# bldc.net
KiCad netlist of a schematic drawn in EAGLE
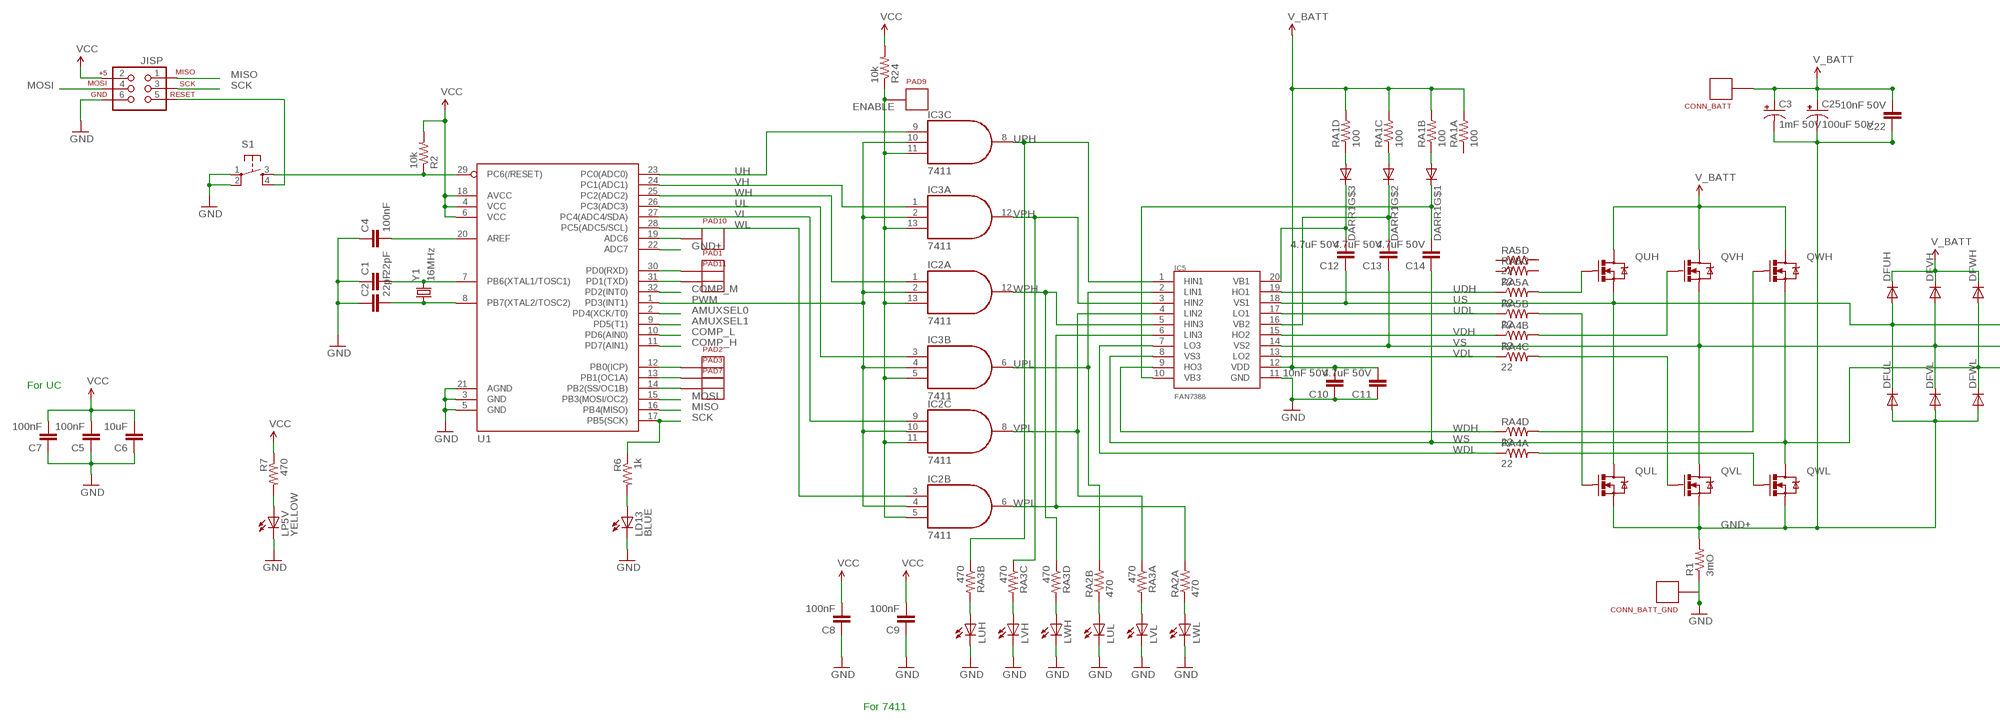
[diagram p0: schematic, sheet 1, part 1 of 2]
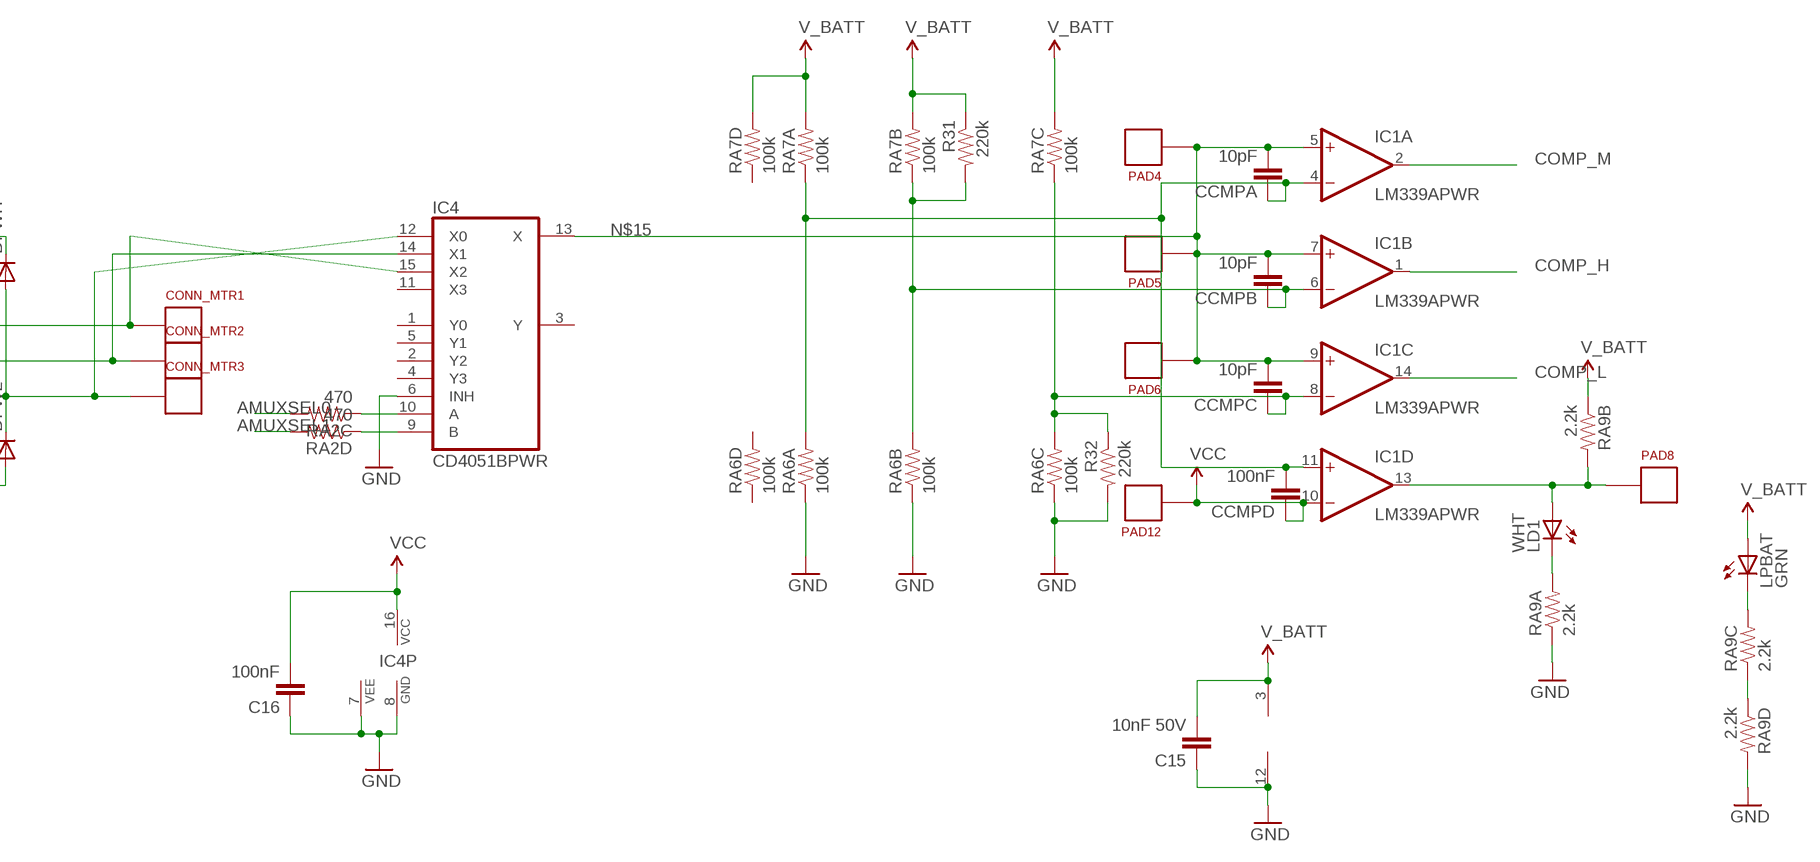
[diagram p1: schematic, sheet 1, part 2 of 2]

(export (version "E")
  (design (tool "Eeschema 10.0.6"))
  (components
    (comp (ref "C1")
      (value "22pF")
      (footprint "eagle-import:0402-CAP")
      (libsource (lib "eagle-import") (part "10NF-CER"))
    )
    (comp (ref "C2")
      (value "22pF")
      (footprint "eagle-import:0402-CAP")
      (libsource (lib "eagle-import") (part "10NF-CER"))
    )
    (comp (ref "C3")
      (value "1mF 50V")
      (footprint "eagle-import:CPOL-RADIAL-1000UF-50V")
      (libsource (lib "eagle-import") (part "CAP_POLPTH5"))
    )
    (comp (ref "C4")
      (value "100nF")
      (footprint "eagle-import:0402-CAP")
      (libsource (lib "eagle-import") (part "10NF-CER"))
    )
    (comp (ref "C5")
      (value "100nF")
      (footprint "eagle-import:0402-CAP")
      (libsource (lib "eagle-import") (part "10NF-CER"))
    )
    (comp (ref "C6")
      (value "10uF")
      (footprint "eagle-import:0805")
      (libsource (lib "eagle-import") (part "22UF-6.3V-20%(0805)"))
    )
    (comp (ref "C7")
      (value "100nF")
      (footprint "eagle-import:0402-CAP")
      (libsource (lib "eagle-import") (part "10NF-CER"))
    )
    (comp (ref "C8")
      (value "100nF")
      (footprint "eagle-import:0402-CAP")
      (libsource (lib "eagle-import") (part "10NF-CER"))
    )
    (comp (ref "C9")
      (value "100nF")
      (footprint "eagle-import:0402-CAP")
      (libsource (lib "eagle-import") (part "10NF-CER"))
    )
    (comp (ref "C10")
      (value "10nF 50V")
      (footprint "eagle-import:0402-CAP")
      (libsource (lib "eagle-import") (part "10NF-CER"))
    )
    (comp (ref "C11")
      (value "4.7uF 50V")
      (footprint "eagle-import:0805")
      (libsource (lib "eagle-import") (part "22UF-6.3V-20%(0805)"))
    )
    (comp (ref "C12")
      (value "4.7uF 50V")
      (footprint "eagle-import:0805")
      (fields (field (name "VOLTAGE") "40"))
      (libsource (lib "eagle-import") (part "22UF-6.3V-20%(0805)"))
    )
    (comp (ref "C13")
      (value "4.7uF 50V")
      (footprint "eagle-import:0805")
      (fields (field (name "VOLTAGE") "40"))
      (libsource (lib "eagle-import") (part "22UF-6.3V-20%(0805)"))
    )
    (comp (ref "C14")
      (value "4.7uF 50V")
      (footprint "eagle-import:0805")
      (fields (field (name "VOLTAGE") "40"))
      (libsource (lib "eagle-import") (part "22UF-6.3V-20%(0805)"))
    )
    (comp (ref "C15")
      (value "10nF 50V")
      (footprint "eagle-import:0402-CAP")
      (libsource (lib "eagle-import") (part "10NF-CER"))
    )
    (comp (ref "C16")
      (value "100nF")
      (footprint "eagle-import:0402-CAP")
      (libsource (lib "eagle-import") (part "10NF-CER"))
    )
    (comp (ref "C22")
      (value "10nF 50V")
      (footprint "eagle-import:0402-CAP")
      (libsource (lib "eagle-import") (part "10NF-CER"))
    )
    (comp (ref "C25")
      (value "100uF 50V")
      (footprint "eagle-import:CPOL-RADIAL-100UF-25V")
      (libsource (lib "eagle-import") (part "CAP_POLPTH1"))
    )
    (comp (ref "CCMPA")
      (value "10pF")
      (footprint "eagle-import:0402-CAP")
      (libsource (lib "eagle-import") (part "10NF-CER"))
    )
    (comp (ref "CCMPB")
      (value "10pF")
      (footprint "eagle-import:0402-CAP")
      (libsource (lib "eagle-import") (part "10NF-CER"))
    )
    (comp (ref "CCMPC")
      (value "10pF")
      (footprint "eagle-import:0402-CAP")
      (libsource (lib "eagle-import") (part "10NF-CER"))
    )
    (comp (ref "CCMPD")
      (value "100nF")
      (footprint "eagle-import:0402-CAP")
      (libsource (lib "eagle-import") (part "10NF-CER"))
    )
    (comp (ref "CONN_BATT")
      (value "CONNECTOR18AWG")
      (footprint "eagle-import:HOLE_18AWG")
      (libsource (lib "eagle-import") (part "CONNECTOR18AWG"))
    )
    (comp (ref "CONN_BATT_GND")
      (value "CONNECTOR18AWG")
      (footprint "eagle-import:HOLE_18AWG")
      (libsource (lib "eagle-import") (part "CONNECTOR18AWG"))
    )
    (comp (ref "CONN_MTR1")
      (value "CONNECTOR18AWG")
      (footprint "eagle-import:HOLE_18AWG")
      (libsource (lib "eagle-import") (part "CONNECTOR18AWG"))
    )
    (comp (ref "CONN_MTR2")
      (value "CONNECTOR18AWG")
      (footprint "eagle-import:HOLE_18AWG")
      (libsource (lib "eagle-import") (part "CONNECTOR18AWG"))
    )
    (comp (ref "CONN_MTR3")
      (value "CONNECTOR18AWG")
      (footprint "eagle-import:HOLE_18AWG")
      (libsource (lib "eagle-import") (part "CONNECTOR18AWG"))
    )
    (comp (ref "DARR1")
      (value "SD103ATW-7-F")
      (footprint "eagle-import:SOT363")
      (libsource (lib "eagle-import") (part "SD103ATW-7-F"))
    )
    (comp (ref "DFUH")
      (value "DIODESOD123W")
      (footprint "eagle-import:SOD123W(NXP)")
      (libsource (lib "eagle-import") (part "DIODESOD123W"))
    )
    (comp (ref "DFUL")
      (value "DIODESOD123W")
      (footprint "eagle-import:SOD123W(NXP)")
      (libsource (lib "eagle-import") (part "DIODESOD123W"))
    )
    (comp (ref "DFVH")
      (value "DIODESOD123W")
      (footprint "eagle-import:SOD123W(NXP)")
      (libsource (lib "eagle-import") (part "DIODESOD123W"))
    )
    (comp (ref "DFVL")
      (value "DIODESOD123W")
      (footprint "eagle-import:SOD123W(NXP)")
      (libsource (lib "eagle-import") (part "DIODESOD123W"))
    )
    (comp (ref "DFWH")
      (value "DIODESOD123W")
      (footprint "eagle-import:SOD123W(NXP)")
      (libsource (lib "eagle-import") (part "DIODESOD123W"))
    )
    (comp (ref "DFWL")
      (value "DIODESOD123W")
      (footprint "eagle-import:SOD123W(NXP)")
      (libsource (lib "eagle-import") (part "DIODESOD123W"))
    )
    (comp (ref "IC1")
      (value "LM339APWR")
      (footprint "eagle-import:TSSOP14")
      (libsource (lib "eagle-import") (part "LM339"))
    )
    (comp (ref "IC2")
      (value "7411")
      (footprint "eagle-import:TSSOP14")
      (libsource (lib "eagle-import") (part "7411"))
    )
    (comp (ref "IC3")
      (value "7411")
      (footprint "eagle-import:TSSOP14")
      (libsource (lib "eagle-import") (part "7411"))
    )
    (comp (ref "IC4")
      (value "CD4051BPWR")
      (footprint "eagle-import:TSSOP16")
      (libsource (lib "eagle-import") (part "4052"))
    )
    (comp (ref "IC5")
      (value "FAN7388")
      (footprint "eagle-import:SO20W")
      (libsource (lib "eagle-import") (part "FAN7388"))
    )
    (comp (ref "JISP")
      (value "AVR_SPI_PRG_6PTH")
      (footprint "eagle-import:2X3")
      (libsource (lib "eagle-import") (part "AVR_SPI_PRG_6PTH"))
    )
    (comp (ref "LD1")
      (value "WHT")
      (footprint "eagle-import:0603_LED")
      (libsource (lib "eagle-import") (part "LED0603"))
    )
    (comp (ref "LD13")
      (value "BLUE")
      (footprint "eagle-import:0603_LED")
      (libsource (lib "eagle-import") (part "LED0603"))
    )
    (comp (ref "LP5V")
      (value "YELLOW")
      (footprint "eagle-import:0603_LED")
      (libsource (lib "eagle-import") (part "LED0603"))
    )
    (comp (ref "LPBAT")
      (value "GRN")
      (footprint "eagle-import:0603_LED")
      (libsource (lib "eagle-import") (part "LED0603"))
    )
    (comp (ref "LUH")
      (value "LED0603")
      (footprint "eagle-import:0603_LED")
      (libsource (lib "eagle-import") (part "LED0603"))
    )
    (comp (ref "LUL")
      (value "LED0603")
      (footprint "eagle-import:0603_LED")
      (libsource (lib "eagle-import") (part "LED0603"))
    )
    (comp (ref "LVH")
      (value "LED0603")
      (footprint "eagle-import:0603_LED")
      (libsource (lib "eagle-import") (part "LED0603"))
    )
    (comp (ref "LVL")
      (value "LED0603")
      (footprint "eagle-import:0603_LED")
      (libsource (lib "eagle-import") (part "LED0603"))
    )
    (comp (ref "LWH")
      (value "LED0603")
      (footprint "eagle-import:0603_LED")
      (libsource (lib "eagle-import") (part "LED0603"))
    )
    (comp (ref "LWL")
      (value "LED0603")
      (footprint "eagle-import:0603_LED")
      (libsource (lib "eagle-import") (part "LED0603"))
    )
    (comp (ref "PAD1")
      (value "PD0")
      (footprint "eagle-import:TESTPAD")
      (libsource (lib "eagle-import") (part "CONNECTOR"))
    )
    (comp (ref "PAD2")
      (value "PB0")
      (footprint "eagle-import:TESTPAD")
      (libsource (lib "eagle-import") (part "CONNECTOR"))
    )
    (comp (ref "PAD3")
      (value "PB1")
      (footprint "eagle-import:TESTPAD")
      (libsource (lib "eagle-import") (part "CONNECTOR"))
    )
    (comp (ref "PAD4")
      (value "CMPA")
      (footprint "eagle-import:TESTPAD")
      (libsource (lib "eagle-import") (part "CONNECTOR"))
    )
    (comp (ref "PAD5")
      (value "CMPB")
      (footprint "eagle-import:TESTPAD")
      (libsource (lib "eagle-import") (part "CONNECTOR"))
    )
    (comp (ref "PAD6")
      (value "CMPC")
      (footprint "eagle-import:TESTPAD")
      (libsource (lib "eagle-import") (part "CONNECTOR"))
    )
    (comp (ref "PAD7")
      (value "PB2")
      (footprint "eagle-import:TESTPAD")
      (libsource (lib "eagle-import") (part "CONNECTOR"))
    )
    (comp (ref "PAD8")
      (value "PGD")
      (footprint "eagle-import:TESTPAD")
      (libsource (lib "eagle-import") (part "CONNECTOR"))
    )
    (comp (ref "PAD9")
      (value "ENBL")
      (footprint "eagle-import:TESTPAD")
      (libsource (lib "eagle-import") (part "CONNECTOR"))
    )
    (comp (ref "PAD10")
      (value "ADC6")
      (footprint "eagle-import:TESTPAD")
      (libsource (lib "eagle-import") (part "CONNECTOR"))
    )
    (comp (ref "PAD11")
      (value "PD1")
      (footprint "eagle-import:TESTPAD")
      (libsource (lib "eagle-import") (part "CONNECTOR"))
    )
    (comp (ref "PAD12")
      (value "VREF")
      (footprint "eagle-import:TESTPAD")
      (libsource (lib "eagle-import") (part "CONNECTOR"))
    )
    (comp (ref "QUH")
      (value "NXP_LFPAK_NFET")
      (footprint "eagle-import:POWERSO8")
      (libsource (lib "eagle-import") (part "NXP_LFPAK_NFET"))
    )
    (comp (ref "QUL")
      (value "NXP_LFPAK_NFET")
      (footprint "eagle-import:POWERSO8")
      (libsource (lib "eagle-import") (part "NXP_LFPAK_NFET"))
    )
    (comp (ref "QVH")
      (value "NXP_LFPAK_NFET")
      (footprint "eagle-import:POWERSO8")
      (libsource (lib "eagle-import") (part "NXP_LFPAK_NFET"))
    )
    (comp (ref "QVL")
      (value "NXP_LFPAK_NFET")
      (footprint "eagle-import:POWERSO8")
      (libsource (lib "eagle-import") (part "NXP_LFPAK_NFET"))
    )
    (comp (ref "QWH")
      (value "NXP_LFPAK_NFET")
      (footprint "eagle-import:POWERSO8")
      (libsource (lib "eagle-import") (part "NXP_LFPAK_NFET"))
    )
    (comp (ref "QWL")
      (value "NXP_LFPAK_NFET")
      (footprint "eagle-import:POWERSO8")
      (libsource (lib "eagle-import") (part "NXP_LFPAK_NFET"))
    )
    (comp (ref "R1")
      (value "3mO")
      (footprint "eagle-import:OAR5")
      (libsource (lib "eagle-import") (part "RESISTOROAR5"))
    )
    (comp (ref "R2")
      (value "10k")
      (footprint "eagle-import:0603-RES")
      (libsource (lib "eagle-import") (part "RESISTOR0603-RES"))
    )
    (comp (ref "R6")
      (value "1k")
      (footprint "eagle-import:0603-RES")
      (libsource (lib "eagle-import") (part "RESISTOR0603-RES"))
    )
    (comp (ref "R7")
      (value "470")
      (footprint "eagle-import:0603-RES")
      (libsource (lib "eagle-import") (part "RESISTOR0603-RES"))
    )
    (comp (ref "R24")
      (value "10k")
      (footprint "eagle-import:0603-RES")
      (libsource (lib "eagle-import") (part "RESISTOR0603-RES"))
    )
    (comp (ref "R31")
      (value "220k")
      (footprint "eagle-import:0603-RES")
      (libsource (lib "eagle-import") (part "RESISTOR0603-RES"))
    )
    (comp (ref "R32")
      (value "220k")
      (footprint "eagle-import:0603-RES")
      (libsource (lib "eagle-import") (part "RESISTOR0603-RES"))
    )
    (comp (ref "RA1")
      (value "100")
      (footprint "eagle-import:0603-ARV")
      (libsource (lib "eagle-import") (part "RESISTOR_ARRAY0603_X4"))
    )
    (comp (ref "RA2")
      (value "470")
      (footprint "eagle-import:0603-ARV")
      (libsource (lib "eagle-import") (part "RESISTOR_ARRAY0603_X4"))
    )
    (comp (ref "RA3")
      (value "470")
      (footprint "eagle-import:0603-ARV")
      (libsource (lib "eagle-import") (part "RESISTOR_ARRAY0603_X4"))
    )
    (comp (ref "RA4")
      (value "22")
      (footprint "eagle-import:0603-ARV")
      (libsource (lib "eagle-import") (part "RESISTOR_ARRAY0603_X4"))
    )
    (comp (ref "RA5")
      (value "22")
      (footprint "eagle-import:0603-ARV")
      (libsource (lib "eagle-import") (part "RESISTOR_ARRAY0603_X4"))
    )
    (comp (ref "RA6")
      (value "100k")
      (footprint "eagle-import:0603-ARV")
      (libsource (lib "eagle-import") (part "RESISTOR_ARRAY0603_X4"))
    )
    (comp (ref "RA7")
      (value "100k")
      (footprint "eagle-import:0603-ARV")
      (libsource (lib "eagle-import") (part "RESISTOR_ARRAY0603_X4"))
    )
    (comp (ref "RA9")
      (value "2.2k")
      (footprint "eagle-import:0603-ARV")
      (libsource (lib "eagle-import") (part "RESISTOR_ARRAY0603_X4"))
    )
    (comp (ref "S1")
      (value "TAC_SWITCHPTH")
      (footprint "eagle-import:TACTILE-PTH")
      (libsource (lib "eagle-import") (part "TAC_SWITCHPTH"))
    )
    (comp (ref "U1")
      (value "ATMEGA328_SMT")
      (footprint "eagle-import:TQFP32-08")
      (libsource (lib "eagle-import") (part "ATMEGA328_SMT"))
    )
    (comp (ref "Y1")
      (value "16MHz")
      (footprint "eagle-import:HC49UP")
      (libsource (lib "eagle-import") (part "CRYSTALSMD"))
    )
  )
  (nets
    (net (code "1") (name "/AMUXSEL0") (class "Default")
      (node (ref "RA2") (pin "6") (pinfunction "2_6") (pintype "passive"))
      (node (ref "U1") (pin "2") (pinfunction "PD4(XCK/T0)_2") (pintype "bidirectional"))
    )
    (net (code "2") (name "/AMUXSEL1") (class "Default")
      (node (ref "RA2") (pin "5") (pinfunction "2_5") (pintype "passive"))
      (node (ref "U1") (pin "9") (pinfunction "PD5(T1)_9") (pintype "bidirectional"))
    )
    (net (code "3") (name "/COMP_H") (class "Default")
      (node (ref "IC1") (pin "1") (pinfunction "OUT_1") (pintype "open_collector"))
      (node (ref "U1") (pin "11") (pinfunction "PD7(AIN1)_11") (pintype "bidirectional"))
    )
    (net (code "4") (name "/COMP_L") (class "Default")
      (node (ref "IC1") (pin "14") (pinfunction "OUT_14") (pintype "open_collector"))
      (node (ref "U1") (pin "10") (pinfunction "PD6(AIN0)_10") (pintype "bidirectional"))
    )
    (net (code "5") (name "/COMP_M") (class "Default")
      (node (ref "IC1") (pin "2") (pinfunction "OUT_2") (pintype "open_collector"))
      (node (ref "U1") (pin "32") (pinfunction "PD2(INT0)_32") (pintype "bidirectional"))
    )
    (net (code "6") (name "/ENABLE") (class "Default")
      (node (ref "IC2") (pin "11") (pinfunction "I2_11") (pintype "input"))
      (node (ref "IC2") (pin "13") (pinfunction "I2_13") (pintype "input"))
      (node (ref "IC2") (pin "5") (pinfunction "I2_5") (pintype "input"))
      (node (ref "IC3") (pin "11") (pinfunction "I2_11") (pintype "input"))
      (node (ref "IC3") (pin "13") (pinfunction "I2_13") (pintype "input"))
      (node (ref "IC3") (pin "5") (pinfunction "I2_5") (pintype "input"))
      (node (ref "PAD9") (pin "P") (pinfunction "P_P") (pintype "bidirectional"))
      (node (ref "R24") (pin "1") (pinfunction "1_1") (pintype "passive"))
    )
    (net (code "7") (name "/GND+") (class "Default")
      (node (ref "C22") (pin "1") (pinfunction "1_1") (pintype "passive"))
      (node (ref "C25") (pin "2") (pinfunction "-_2") (pintype "passive"))
      (node (ref "C3") (pin "2") (pinfunction "-_2") (pintype "passive"))
      (node (ref "DFUL") (pin "A") (pinfunction "A_A") (pintype "passive"))
      (node (ref "DFVL") (pin "A") (pinfunction "A_A") (pintype "passive"))
      (node (ref "DFWL") (pin "A") (pinfunction "A_A") (pintype "passive"))
      (node (ref "QUL") (pin "P1") (pinfunction "S_P1") (pintype "passive"))
      (node (ref "QUL") (pin "P2") (pinfunction "S_P2") (pintype "passive"))
      (node (ref "QUL") (pin "P3") (pinfunction "S_P3") (pintype "passive"))
      (node (ref "QVL") (pin "P1") (pinfunction "S_P1") (pintype "passive"))
      (node (ref "QVL") (pin "P2") (pinfunction "S_P2") (pintype "passive"))
      (node (ref "QVL") (pin "P3") (pinfunction "S_P3") (pintype "passive"))
      (node (ref "QWL") (pin "P1") (pinfunction "S_P1") (pintype "passive"))
      (node (ref "QWL") (pin "P2") (pinfunction "S_P2") (pintype "passive"))
      (node (ref "QWL") (pin "P3") (pinfunction "S_P3") (pintype "passive"))
      (node (ref "R1") (pin "P$2") (pinfunction "2_P$2") (pintype "passive"))
      (node (ref "U1") (pin "22") (pinfunction "ADC7_22") (pintype "bidirectional"))
    )
    (net (code "8") (name "/MISO") (class "Default")
      (node (ref "JISP") (pin "1") (pinfunction "1_1") (pintype "passive"))
      (node (ref "U1") (pin "16") (pinfunction "PB4(MISO)_16") (pintype "bidirectional"))
    )
    (net (code "9") (name "/MOSI") (class "Default")
      (node (ref "JISP") (pin "4") (pinfunction "4_4") (pintype "passive"))
      (node (ref "U1") (pin "15") (pinfunction "PB3(MOSI/OC2)_15") (pintype "bidirectional"))
    )
    (net (code "10") (name "/N$15") (class "Default")
      (node (ref "CCMPA") (pin "2") (pinfunction "2_2") (pintype "passive"))
      (node (ref "CCMPB") (pin "2") (pinfunction "2_2") (pintype "passive"))
      (node (ref "CCMPC") (pin "2") (pinfunction "2_2") (pintype "passive"))
      (node (ref "IC1") (pin "5") (pinfunction "+IN_5") (pintype "input"))
      (node (ref "IC1") (pin "7") (pinfunction "+IN_7") (pintype "input"))
      (node (ref "IC1") (pin "9") (pinfunction "+IN_9") (pintype "input"))
      (node (ref "IC4") (pin "13") (pinfunction "X_13") (pintype "bidirectional"))
      (node (ref "PAD4") (pin "P") (pinfunction "P_P") (pintype "bidirectional"))
      (node (ref "PAD5") (pin "P") (pinfunction "P_P") (pintype "bidirectional"))
      (node (ref "PAD6") (pin "P") (pinfunction "P_P") (pintype "bidirectional"))
    )
    (net (code "11") (name "/PWM") (class "Default")
      (node (ref "IC2") (pin "10") (pinfunction "I1_10") (pintype "input"))
      (node (ref "IC2") (pin "2") (pinfunction "I1_2") (pintype "input"))
      (node (ref "IC2") (pin "4") (pinfunction "I1_4") (pintype "input"))
      (node (ref "IC3") (pin "10") (pinfunction "I1_10") (pintype "input"))
      (node (ref "IC3") (pin "2") (pinfunction "I1_2") (pintype "input"))
      (node (ref "IC3") (pin "4") (pinfunction "I1_4") (pintype "input"))
      (node (ref "U1") (pin "1") (pinfunction "PD3(INT1)_1") (pintype "bidirectional"))
    )
    (net (code "12") (name "/SCK") (class "Default")
      (node (ref "JISP") (pin "3") (pinfunction "3_3") (pintype "passive"))
      (node (ref "R6") (pin "1") (pinfunction "1_1") (pintype "passive"))
      (node (ref "U1") (pin "17") (pinfunction "PB5(SCK)_17") (pintype "bidirectional"))
    )
    (net (code "13") (name "/UDH") (class "Default")
      (node (ref "IC5") (pin "19") (pinfunction "HO1_19") (pintype "bidirectional"))
      (node (ref "RA5") (pin "1") (pinfunction "1_1") (pintype "passive"))
    )
    (net (code "14") (name "/UDL") (class "Default")
      (node (ref "IC5") (pin "17") (pinfunction "LO1_17") (pintype "bidirectional"))
      (node (ref "RA5") (pin "2") (pinfunction "1_2") (pintype "passive"))
    )
    (net (code "15") (name "/UH") (class "Default")
      (node (ref "IC3") (pin "9") (pinfunction "I0_9") (pintype "input"))
      (node (ref "U1") (pin "23") (pinfunction "PC0(ADC0)_23") (pintype "bidirectional"))
    )
    (net (code "16") (name "/UL") (class "Default")
      (node (ref "IC3") (pin "3") (pinfunction "I0_3") (pintype "input"))
      (node (ref "U1") (pin "26") (pinfunction "PC3(ADC3)_26") (pintype "bidirectional"))
    )
    (net (code "17") (name "/UPH") (class "Default")
      (node (ref "IC3") (pin "8") (pinfunction "O_8") (pintype "output"))
      (node (ref "IC5") (pin "1") (pinfunction "HIN1_1") (pintype "bidirectional"))
      (node (ref "RA3") (pin "2") (pinfunction "1_2") (pintype "passive"))
    )
    (net (code "18") (name "/UPL") (class "Default")
      (node (ref "IC3") (pin "6") (pinfunction "O_6") (pintype "output"))
      (node (ref "IC5") (pin "2") (pinfunction "LIN1_2") (pintype "bidirectional"))
      (node (ref "RA2") (pin "7") (pinfunction "2_7") (pintype "passive"))
    )
    (net (code "19") (name "/US") (class "Default")
      (node (ref "C12") (pin "1") (pinfunction "1_1") (pintype "passive"))
      (node (ref "CONN_MTR1") (pin "P$1") (pinfunction "P_P$1") (pintype "bidirectional"))
      (node (ref "DFUH") (pin "A") (pinfunction "A_A") (pintype "passive"))
      (node (ref "DFUL") (pin "C") (pinfunction "C_C") (pintype "passive"))
      (node (ref "IC4") (pin "15") (pinfunction "X2_15") (pintype "bidirectional"))
      (node (ref "IC5") (pin "18") (pinfunction "VS1_18") (pintype "bidirectional"))
      (node (ref "QUH") (pin "P1") (pinfunction "S_P1") (pintype "passive"))
      (node (ref "QUH") (pin "P2") (pinfunction "S_P2") (pintype "passive"))
      (node (ref "QUH") (pin "P3") (pinfunction "S_P3") (pintype "passive"))
      (node (ref "QUL") (pin "P$1") (pinfunction "D_P$1") (pintype "passive"))
      (node (ref "QUL") (pin "P$10") (pinfunction "D_P$10") (pintype "passive"))
      (node (ref "QUL") (pin "P$11") (pinfunction "D_P$11") (pintype "passive"))
      (node (ref "QUL") (pin "P$12") (pinfunction "D_P$12") (pintype "passive"))
      (node (ref "QUL") (pin "P$13") (pinfunction "D_P$13") (pintype "passive"))
      (node (ref "QUL") (pin "P$14") (pinfunction "D_P$14") (pintype "passive"))
      (node (ref "QUL") (pin "P$15") (pinfunction "D_P$15") (pintype "passive"))
      (node (ref "QUL") (pin "P$16") (pinfunction "D_P$16") (pintype "passive"))
      (node (ref "QUL") (pin "P$17") (pinfunction "D_P$17") (pintype "passive"))
      (node (ref "QUL") (pin "P$19") (pinfunction "D_P$19") (pintype "passive"))
      (node (ref "QUL") (pin "P$20") (pinfunction "D_P$20") (pintype "passive"))
      (node (ref "QUL") (pin "P$21") (pinfunction "D_P$21") (pintype "passive"))
      (node (ref "QUL") (pin "P$5") (pinfunction "D_P$5") (pintype "passive"))
      (node (ref "QUL") (pin "P$6") (pinfunction "D_P$6") (pintype "passive"))
      (node (ref "QUL") (pin "P$7") (pinfunction "D_P$7") (pintype "passive"))
      (node (ref "QUL") (pin "P$8") (pinfunction "D_P$8") (pintype "passive"))
      (node (ref "QUL") (pin "P$9") (pinfunction "D_P$9") (pintype "passive"))
    )
    (net (code "20") (name "/VDH") (class "Default")
      (node (ref "IC5") (pin "15") (pinfunction "HO2_15") (pintype "bidirectional"))
      (node (ref "RA4") (pin "2") (pinfunction "1_2") (pintype "passive"))
    )
    (net (code "21") (name "/VDL") (class "Default")
      (node (ref "IC5") (pin "13") (pinfunction "LO2_13") (pintype "bidirectional"))
      (node (ref "RA4") (pin "3") (pinfunction "1_3") (pintype "passive"))
    )
    (net (code "22") (name "/VH") (class "Default")
      (node (ref "IC3") (pin "1") (pinfunction "I0_1") (pintype "input"))
      (node (ref "U1") (pin "24") (pinfunction "PC1(ADC1)_24") (pintype "bidirectional"))
    )
    (net (code "23") (name "/VL") (class "Default")
      (node (ref "IC2") (pin "9") (pinfunction "I0_9") (pintype "input"))
      (node (ref "U1") (pin "27") (pinfunction "PC4(ADC4/SDA)_27") (pintype "bidirectional"))
    )
    (net (code "24") (name "/VPH") (class "Default")
      (node (ref "IC3") (pin "12") (pinfunction "O_12") (pintype "output"))
      (node (ref "IC5") (pin "3") (pinfunction "HIN2_3") (pintype "bidirectional"))
      (node (ref "RA3") (pin "3") (pinfunction "1_3") (pintype "passive"))
    )
    (net (code "25") (name "/VPL") (class "Default")
      (node (ref "IC2") (pin "8") (pinfunction "O_8") (pintype "output"))
      (node (ref "IC5") (pin "4") (pinfunction "LIN2_4") (pintype "bidirectional"))
      (node (ref "RA3") (pin "1") (pinfunction "1_1") (pintype "passive"))
    )
    (net (code "26") (name "/VS") (class "Default")
      (node (ref "C13") (pin "1") (pinfunction "1_1") (pintype "passive"))
      (node (ref "CONN_MTR2") (pin "P$1") (pinfunction "P_P$1") (pintype "bidirectional"))
      (node (ref "DFVH") (pin "A") (pinfunction "A_A") (pintype "passive"))
      (node (ref "DFVL") (pin "C") (pinfunction "C_C") (pintype "passive"))
      (node (ref "IC4") (pin "14") (pinfunction "X1_14") (pintype "bidirectional"))
      (node (ref "IC5") (pin "14") (pinfunction "VS2_14") (pintype "bidirectional"))
      (node (ref "QVH") (pin "P1") (pinfunction "S_P1") (pintype "passive"))
      (node (ref "QVH") (pin "P2") (pinfunction "S_P2") (pintype "passive"))
      (node (ref "QVH") (pin "P3") (pinfunction "S_P3") (pintype "passive"))
      (node (ref "QVL") (pin "P$1") (pinfunction "D_P$1") (pintype "passive"))
      (node (ref "QVL") (pin "P$10") (pinfunction "D_P$10") (pintype "passive"))
      (node (ref "QVL") (pin "P$11") (pinfunction "D_P$11") (pintype "passive"))
      (node (ref "QVL") (pin "P$12") (pinfunction "D_P$12") (pintype "passive"))
      (node (ref "QVL") (pin "P$13") (pinfunction "D_P$13") (pintype "passive"))
      (node (ref "QVL") (pin "P$14") (pinfunction "D_P$14") (pintype "passive"))
      (node (ref "QVL") (pin "P$15") (pinfunction "D_P$15") (pintype "passive"))
      (node (ref "QVL") (pin "P$16") (pinfunction "D_P$16") (pintype "passive"))
      (node (ref "QVL") (pin "P$17") (pinfunction "D_P$17") (pintype "passive"))
      (node (ref "QVL") (pin "P$19") (pinfunction "D_P$19") (pintype "passive"))
      (node (ref "QVL") (pin "P$20") (pinfunction "D_P$20") (pintype "passive"))
      (node (ref "QVL") (pin "P$21") (pinfunction "D_P$21") (pintype "passive"))
      (node (ref "QVL") (pin "P$5") (pinfunction "D_P$5") (pintype "passive"))
      (node (ref "QVL") (pin "P$6") (pinfunction "D_P$6") (pintype "passive"))
      (node (ref "QVL") (pin "P$7") (pinfunction "D_P$7") (pintype "passive"))
      (node (ref "QVL") (pin "P$8") (pinfunction "D_P$8") (pintype "passive"))
      (node (ref "QVL") (pin "P$9") (pinfunction "D_P$9") (pintype "passive"))
    )
    (net (code "27") (name "/WDH") (class "Default")
      (node (ref "IC5") (pin "9") (pinfunction "HO3_9") (pintype "bidirectional"))
      (node (ref "RA4") (pin "4") (pinfunction "1_4") (pintype "passive"))
    )
    (net (code "28") (name "/WDL") (class "Default")
      (node (ref "IC5") (pin "7") (pinfunction "LO3_7") (pintype "bidirectional"))
      (node (ref "RA4") (pin "1") (pinfunction "1_1") (pintype "passive"))
    )
    (net (code "29") (name "/WH") (class "Default")
      (node (ref "IC2") (pin "1") (pinfunction "I0_1") (pintype "input"))
      (node (ref "U1") (pin "25") (pinfunction "PC2(ADC2)_25") (pintype "bidirectional"))
    )
    (net (code "30") (name "/WL") (class "Default")
      (node (ref "IC2") (pin "3") (pinfunction "I0_3") (pintype "input"))
      (node (ref "U1") (pin "28") (pinfunction "PC5(ADC5/SCL)_28") (pintype "bidirectional"))
    )
    (net (code "31") (name "/WPH") (class "Default")
      (node (ref "IC2") (pin "12") (pinfunction "O_12") (pintype "output"))
      (node (ref "IC5") (pin "5") (pinfunction "HIN3_5") (pintype "bidirectional"))
      (node (ref "RA3") (pin "4") (pinfunction "1_4") (pintype "passive"))
    )
    (net (code "32") (name "/WPL") (class "Default")
      (node (ref "IC2") (pin "6") (pinfunction "O_6") (pintype "output"))
      (node (ref "IC5") (pin "6") (pinfunction "LIN3_6") (pintype "bidirectional"))
      (node (ref "RA2") (pin "8") (pinfunction "2_8") (pintype "passive"))
    )
    (net (code "33") (name "/WS") (class "Default")
      (node (ref "C14") (pin "1") (pinfunction "1_1") (pintype "passive"))
      (node (ref "CONN_MTR3") (pin "P$1") (pinfunction "P_P$1") (pintype "bidirectional"))
      (node (ref "DFWH") (pin "A") (pinfunction "A_A") (pintype "passive"))
      (node (ref "DFWL") (pin "C") (pinfunction "C_C") (pintype "passive"))
      (node (ref "IC4") (pin "12") (pinfunction "X0_12") (pintype "bidirectional"))
      (node (ref "IC5") (pin "8") (pinfunction "VS3_8") (pintype "bidirectional"))
      (node (ref "QWH") (pin "P1") (pinfunction "S_P1") (pintype "passive"))
      (node (ref "QWH") (pin "P2") (pinfunction "S_P2") (pintype "passive"))
      (node (ref "QWH") (pin "P3") (pinfunction "S_P3") (pintype "passive"))
      (node (ref "QWL") (pin "P$1") (pinfunction "D_P$1") (pintype "passive"))
      (node (ref "QWL") (pin "P$10") (pinfunction "D_P$10") (pintype "passive"))
      (node (ref "QWL") (pin "P$11") (pinfunction "D_P$11") (pintype "passive"))
      (node (ref "QWL") (pin "P$12") (pinfunction "D_P$12") (pintype "passive"))
      (node (ref "QWL") (pin "P$13") (pinfunction "D_P$13") (pintype "passive"))
      (node (ref "QWL") (pin "P$14") (pinfunction "D_P$14") (pintype "passive"))
      (node (ref "QWL") (pin "P$15") (pinfunction "D_P$15") (pintype "passive"))
      (node (ref "QWL") (pin "P$16") (pinfunction "D_P$16") (pintype "passive"))
      (node (ref "QWL") (pin "P$17") (pinfunction "D_P$17") (pintype "passive"))
      (node (ref "QWL") (pin "P$19") (pinfunction "D_P$19") (pintype "passive"))
      (node (ref "QWL") (pin "P$20") (pinfunction "D_P$20") (pintype "passive"))
      (node (ref "QWL") (pin "P$21") (pinfunction "D_P$21") (pintype "passive"))
      (node (ref "QWL") (pin "P$5") (pinfunction "D_P$5") (pintype "passive"))
      (node (ref "QWL") (pin "P$6") (pinfunction "D_P$6") (pintype "passive"))
      (node (ref "QWL") (pin "P$7") (pinfunction "D_P$7") (pintype "passive"))
      (node (ref "QWL") (pin "P$8") (pinfunction "D_P$8") (pintype "passive"))
      (node (ref "QWL") (pin "P$9") (pinfunction "D_P$9") (pintype "passive"))
    )
    (net (code "34") (name "GND") (class "Default")
      (node (ref "C1") (pin "1") (pinfunction "1_1") (pintype "passive"))
      (node (ref "C10") (pin "1") (pinfunction "1_1") (pintype "passive"))
      (node (ref "C11") (pin "1") (pinfunction "1_1") (pintype "passive"))
      (node (ref "C15") (pin "1") (pinfunction "1_1") (pintype "passive"))
      (node (ref "C16") (pin "1") (pinfunction "1_1") (pintype "passive"))
      (node (ref "C2") (pin "1") (pinfunction "1_1") (pintype "passive"))
      (node (ref "C4") (pin "1") (pinfunction "1_1") (pintype "passive"))
      (node (ref "C5") (pin "1") (pinfunction "1_1") (pintype "passive"))
      (node (ref "C6") (pin "1") (pinfunction "1_1") (pintype "passive"))
      (node (ref "C7") (pin "1") (pinfunction "1_1") (pintype "passive"))
      (node (ref "C8") (pin "1") (pinfunction "1_1") (pintype "passive"))
      (node (ref "C9") (pin "1") (pinfunction "1_1") (pintype "passive"))
      (node (ref "CONN_BATT_GND") (pin "P$1") (pinfunction "P_P$1") (pintype "bidirectional"))
      (node (ref "IC1") (pin "12") (pinfunction "GND_12") (pintype "power_in"))
      (node (ref "IC4") (pin "6") (pinfunction "INH_6") (pintype "input"))
      (node (ref "IC4") (pin "7") (pinfunction "VEE_7") (pintype "power_in"))
      (node (ref "IC4") (pin "8") (pinfunction "GND_8") (pintype "power_in"))
      (node (ref "IC5") (pin "11") (pinfunction "GND_11") (pintype "bidirectional"))
      (node (ref "JISP") (pin "6") (pinfunction "6_6") (pintype "passive"))
      (node (ref "LD13") (pin "C") (pinfunction "C_C") (pintype "passive"))
      (node (ref "LP5V") (pin "C") (pinfunction "C_C") (pintype "passive"))
      (node (ref "LUH") (pin "C") (pinfunction "C_C") (pintype "passive"))
      (node (ref "LUL") (pin "C") (pinfunction "C_C") (pintype "passive"))
      (node (ref "LVH") (pin "C") (pinfunction "C_C") (pintype "passive"))
      (node (ref "LVL") (pin "C") (pinfunction "C_C") (pintype "passive"))
      (node (ref "LWH") (pin "C") (pinfunction "C_C") (pintype "passive"))
      (node (ref "LWL") (pin "C") (pinfunction "C_C") (pintype "passive"))
      (node (ref "R1") (pin "P$1") (pinfunction "1_P$1") (pintype "passive"))
      (node (ref "R32") (pin "2") (pinfunction "2_2") (pintype "passive"))
      (node (ref "RA6") (pin "1") (pinfunction "1_1") (pintype "passive"))
      (node (ref "RA6") (pin "2") (pinfunction "1_2") (pintype "passive"))
      (node (ref "RA6") (pin "3") (pinfunction "1_3") (pintype "passive"))
      (node (ref "RA9") (pin "1") (pinfunction "1_1") (pintype "passive"))
      (node (ref "RA9") (pin "5") (pinfunction "2_5") (pintype "passive"))
      (node (ref "S1") (pin "1") (pinfunction "1_1") (pintype "passive"))
      (node (ref "S1") (pin "2") (pinfunction "2_2") (pintype "passive"))
      (node (ref "U1") (pin "21") (pinfunction "AGND_21") (pintype "bidirectional"))
      (node (ref "U1") (pin "3") (pinfunction "GND_3") (pintype "bidirectional"))
      (node (ref "U1") (pin "5") (pinfunction "GND_5") (pintype "bidirectional"))
    )
    (net (code "35") (name "Net-(DARR1A-A)") (class "Default")
      (node (ref "DARR1") (pin "6") (pinfunction "A_6") (pintype "passive"))
      (node (ref "RA1") (pin "2") (pinfunction "1_2") (pintype "passive"))
    )
    (net (code "36") (name "Net-(DARR1A-C)") (class "Default")
      (node (ref "C14") (pin "2") (pinfunction "2_2") (pintype "passive"))
      (node (ref "DARR1") (pin "1") (pinfunction "C_1") (pintype "passive"))
      (node (ref "IC5") (pin "10") (pinfunction "VB3_10") (pintype "bidirectional"))
    )
    (net (code "37") (name "Net-(DARR1B-A)") (class "Default")
      (node (ref "DARR1") (pin "5") (pinfunction "A_5") (pintype "passive"))
      (node (ref "RA1") (pin "3") (pinfunction "1_3") (pintype "passive"))
    )
    (net (code "38") (name "Net-(DARR1B-C)") (class "Default")
      (node (ref "C13") (pin "2") (pinfunction "2_2") (pintype "passive"))
      (node (ref "DARR1") (pin "2") (pinfunction "C_2") (pintype "passive"))
      (node (ref "IC5") (pin "16") (pinfunction "VB2_16") (pintype "bidirectional"))
    )
    (net (code "39") (name "Net-(DARR1C-A)") (class "Default")
      (node (ref "DARR1") (pin "4") (pinfunction "A_4") (pintype "passive"))
      (node (ref "RA1") (pin "4") (pinfunction "1_4") (pintype "passive"))
    )
    (net (code "40") (name "Net-(DARR1C-C)") (class "Default")
      (node (ref "C12") (pin "2") (pinfunction "2_2") (pintype "passive"))
      (node (ref "DARR1") (pin "3") (pinfunction "C_3") (pintype "passive"))
      (node (ref "IC5") (pin "20") (pinfunction "VB1_20") (pintype "bidirectional"))
    )
    (net (code "41") (name "Net-(IC1A--IN)") (class "Default")
      (node (ref "CCMPA") (pin "1") (pinfunction "1_1") (pintype "passive"))
      (node (ref "CCMPD") (pin "2") (pinfunction "2_2") (pintype "passive"))
      (node (ref "IC1") (pin "11") (pinfunction "+IN_11") (pintype "input"))
      (node (ref "IC1") (pin "4") (pinfunction "-IN_4") (pintype "input"))
      (node (ref "RA6") (pin "8") (pinfunction "2_8") (pintype "passive"))
      (node (ref "RA7") (pin "1") (pinfunction "1_1") (pintype "passive"))
    )
    (net (code "42") (name "Net-(IC1B--IN)") (class "Default")
      (node (ref "CCMPB") (pin "1") (pinfunction "1_1") (pintype "passive"))
      (node (ref "IC1") (pin "6") (pinfunction "-IN_6") (pintype "input"))
      (node (ref "R31") (pin "2") (pinfunction "2_2") (pintype "passive"))
      (node (ref "RA6") (pin "7") (pinfunction "2_7") (pintype "passive"))
      (node (ref "RA7") (pin "2") (pinfunction "1_2") (pintype "passive"))
    )
    (net (code "43") (name "Net-(IC1C--IN)") (class "Default")
      (node (ref "CCMPC") (pin "1") (pinfunction "1_1") (pintype "passive"))
      (node (ref "IC1") (pin "8") (pinfunction "-IN_8") (pintype "input"))
      (node (ref "R32") (pin "1") (pinfunction "1_1") (pintype "passive"))
      (node (ref "RA6") (pin "6") (pinfunction "2_6") (pintype "passive"))
      (node (ref "RA7") (pin "3") (pinfunction "1_3") (pintype "passive"))
    )
    (net (code "44") (name "Net-(IC1D-OUT)") (class "Default")
      (node (ref "IC1") (pin "13") (pinfunction "OUT_13") (pintype "open_collector"))
      (node (ref "LD1") (pin "A") (pinfunction "A_A") (pintype "passive"))
      (node (ref "PAD8") (pin "P") (pinfunction "P_P") (pintype "bidirectional"))
      (node (ref "RA9") (pin "7") (pinfunction "2_7") (pintype "passive"))
    )
    (net (code "45") (name "Net-(IC4A-A)") (class "Default")
      (node (ref "IC4") (pin "10") (pinfunction "A_10") (pintype "input"))
      (node (ref "RA2") (pin "3") (pinfunction "1_3") (pintype "passive"))
    )
    (net (code "46") (name "Net-(IC4A-B)") (class "Default")
      (node (ref "IC4") (pin "9") (pinfunction "B_9") (pintype "input"))
      (node (ref "RA2") (pin "4") (pinfunction "1_4") (pintype "passive"))
    )
    (net (code "47") (name "Net-(JISP-Pad5)") (class "Default")
      (node (ref "JISP") (pin "5") (pinfunction "5_5") (pintype "passive"))
      (node (ref "S1") (pin "4") (pinfunction "4_4") (pintype "passive"))
    )
    (net (code "48") (name "Net-(LD13-PadA)") (class "Default")
      (node (ref "LD13") (pin "A") (pinfunction "A_A") (pintype "passive"))
      (node (ref "R6") (pin "2") (pinfunction "2_2") (pintype "passive"))
    )
    (net (code "49") (name "Net-(LP5V-PadA)") (class "Default")
      (node (ref "LP5V") (pin "A") (pinfunction "A_A") (pintype "passive"))
      (node (ref "R7") (pin "2") (pinfunction "2_2") (pintype "passive"))
    )
    (net (code "50") (name "Net-(LWL-PadA)") (class "Default")
      (node (ref "LWL") (pin "A") (pinfunction "A_A") (pintype "passive"))
      (node (ref "RA2") (pin "1") (pinfunction "1_1") (pintype "passive"))
    )
    (net (code "51") (name "Net-(QUH-G)") (class "Default")
      (node (ref "QUH") (pin "P4") (pinfunction "G_P4") (pintype "passive"))
      (node (ref "RA5") (pin "8") (pinfunction "2_8") (pintype "passive"))
    )
    (net (code "52") (name "Net-(QUL-G)") (class "Default")
      (node (ref "QUL") (pin "P4") (pinfunction "G_P4") (pintype "passive"))
      (node (ref "RA5") (pin "7") (pinfunction "2_7") (pintype "passive"))
    )
    (net (code "53") (name "Net-(QVH-G)") (class "Default")
      (node (ref "QVH") (pin "P4") (pinfunction "G_P4") (pintype "passive"))
      (node (ref "RA4") (pin "7") (pinfunction "2_7") (pintype "passive"))
    )
    (net (code "54") (name "Net-(QVL-G)") (class "Default")
      (node (ref "QVL") (pin "P4") (pinfunction "G_P4") (pintype "passive"))
      (node (ref "RA4") (pin "6") (pinfunction "2_6") (pintype "passive"))
    )
    (net (code "55") (name "Net-(QWH-G)") (class "Default")
      (node (ref "QWH") (pin "P4") (pinfunction "G_P4") (pintype "passive"))
      (node (ref "RA4") (pin "5") (pinfunction "2_5") (pintype "passive"))
    )
    (net (code "56") (name "Net-(QWL-G)") (class "Default")
      (node (ref "QWL") (pin "P4") (pinfunction "G_P4") (pintype "passive"))
      (node (ref "RA4") (pin "8") (pinfunction "2_8") (pintype "passive"))
    )
    (net (code "57") (name "Net-(RA2B-1)") (class "Default")
      (node (ref "LUL") (pin "A") (pinfunction "A_A") (pintype "passive"))
      (node (ref "RA2") (pin "2") (pinfunction "1_2") (pintype "passive"))
    )
    (net (code "58") (name "Net-(RA3A-2)") (class "Default")
      (node (ref "LVL") (pin "A") (pinfunction "A_A") (pintype "passive"))
      (node (ref "RA3") (pin "8") (pinfunction "2_8") (pintype "passive"))
    )
    (net (code "59") (name "Net-(RA3B-2)") (class "Default")
      (node (ref "LUH") (pin "A") (pinfunction "A_A") (pintype "passive"))
      (node (ref "RA3") (pin "7") (pinfunction "2_7") (pintype "passive"))
    )
    (net (code "60") (name "Net-(RA3C-2)") (class "Default")
      (node (ref "LVH") (pin "A") (pinfunction "A_A") (pintype "passive"))
      (node (ref "RA3") (pin "6") (pinfunction "2_6") (pintype "passive"))
    )
    (net (code "61") (name "Net-(RA3D-2)") (class "Default")
      (node (ref "LWH") (pin "A") (pinfunction "A_A") (pintype "passive"))
      (node (ref "RA3") (pin "5") (pinfunction "2_5") (pintype "passive"))
    )
    (net (code "62") (name "Net-(RA9A-2)") (class "Default")
      (node (ref "LD1") (pin "C") (pinfunction "C_C") (pintype "passive"))
      (node (ref "RA9") (pin "8") (pinfunction "2_8") (pintype "passive"))
    )
    (net (code "63") (name "Net-(RA9C-1)") (class "Default")
      (node (ref "RA9") (pin "3") (pinfunction "1_3") (pintype "passive"))
      (node (ref "RA9") (pin "4") (pinfunction "1_4") (pintype "passive"))
    )
    (net (code "64") (name "Net-(RA9C-2)") (class "Default")
      (node (ref "LPBAT") (pin "C") (pinfunction "C_C") (pintype "passive"))
      (node (ref "RA9") (pin "6") (pinfunction "2_6") (pintype "passive"))
    )
    (net (code "65") (name "Net-(U1-ADC6)") (class "Default")
      (node (ref "PAD10") (pin "P") (pinfunction "P_P") (pintype "bidirectional"))
      (node (ref "U1") (pin "19") (pinfunction "ADC6_19") (pintype "bidirectional"))
    )
    (net (code "66") (name "Net-(U1-AREF)") (class "Default")
      (node (ref "C4") (pin "2") (pinfunction "2_2") (pintype "passive"))
      (node (ref "U1") (pin "20") (pinfunction "AREF_20") (pintype "bidirectional"))
    )
    (net (code "67") (name "Net-(U1-PB0(ICP))") (class "Default")
      (node (ref "PAD2") (pin "P") (pinfunction "P_P") (pintype "bidirectional"))
      (node (ref "U1") (pin "12") (pinfunction "PB0(ICP)_12") (pintype "bidirectional"))
    )
    (net (code "68") (name "Net-(U1-PB1(OC1A))") (class "Default")
      (node (ref "PAD3") (pin "P") (pinfunction "P_P") (pintype "bidirectional"))
      (node (ref "U1") (pin "13") (pinfunction "PB1(OC1A)_13") (pintype "bidirectional"))
    )
    (net (code "69") (name "Net-(U1-PB2(SS{slash}OC1B))") (class "Default")
      (node (ref "PAD7") (pin "P") (pinfunction "P_P") (pintype "bidirectional"))
      (node (ref "U1") (pin "14") (pinfunction "PB2(SS/OC1B)_14") (pintype "bidirectional"))
    )
    (net (code "70") (name "Net-(U1-PB6(XTAL1{slash}TOSC1))") (class "Default")
      (node (ref "C1") (pin "2") (pinfunction "2_2") (pintype "passive"))
      (node (ref "U1") (pin "7") (pinfunction "PB6(XTAL1/TOSC1)_7") (pintype "bidirectional"))
      (node (ref "Y1") (pin "2") (pinfunction "2_2") (pintype "passive"))
    )
    (net (code "71") (name "Net-(U1-PB7(XTAL2{slash}TOSC2))") (class "Default")
      (node (ref "C2") (pin "2") (pinfunction "2_2") (pintype "passive"))
      (node (ref "U1") (pin "8") (pinfunction "PB7(XTAL2/TOSC2)_8") (pintype "bidirectional"))
      (node (ref "Y1") (pin "1") (pinfunction "1_1") (pintype "passive"))
    )
    (net (code "72") (name "Net-(U1-PC6({slash}RESET))") (class "Default")
      (node (ref "R2") (pin "1") (pinfunction "1_1") (pintype "passive"))
      (node (ref "S1") (pin "3") (pinfunction "3_3") (pintype "passive"))
      (node (ref "U1") (pin "29") (pinfunction "PC6(/RESET)_29") (pintype "bidirectional"))
    )
    (net (code "73") (name "Net-(U1-PD0(RXD))") (class "Default")
      (node (ref "PAD1") (pin "P") (pinfunction "P_P") (pintype "bidirectional"))
      (node (ref "U1") (pin "30") (pinfunction "PD0(RXD)_30") (pintype "bidirectional"))
    )
    (net (code "74") (name "Net-(U1-PD1(TXD))") (class "Default")
      (node (ref "PAD11") (pin "P") (pinfunction "P_P") (pintype "bidirectional"))
      (node (ref "U1") (pin "31") (pinfunction "PD1(TXD)_31") (pintype "bidirectional"))
    )
    (net (code "75") (name "VCC") (class "Default")
      (node (ref "C16") (pin "2") (pinfunction "2_2") (pintype "passive"))
      (node (ref "C5") (pin "2") (pinfunction "2_2") (pintype "passive"))
      (node (ref "C6") (pin "2") (pinfunction "2_2") (pintype "passive"))
      (node (ref "C7") (pin "2") (pinfunction "2_2") (pintype "passive"))
      (node (ref "C8") (pin "2") (pinfunction "2_2") (pintype "passive"))
      (node (ref "C9") (pin "2") (pinfunction "2_2") (pintype "passive"))
      (node (ref "CCMPD") (pin "1") (pinfunction "1_1") (pintype "passive"))
      (node (ref "IC1") (pin "10") (pinfunction "-IN_10") (pintype "input"))
      (node (ref "IC4") (pin "16") (pinfunction "VCC_16") (pintype "power_in"))
      (node (ref "JISP") (pin "2") (pinfunction "2_2") (pintype "passive"))
      (node (ref "PAD12") (pin "P") (pinfunction "P_P") (pintype "bidirectional"))
      (node (ref "R2") (pin "2") (pinfunction "2_2") (pintype "passive"))
      (node (ref "R24") (pin "2") (pinfunction "2_2") (pintype "passive"))
      (node (ref "R7") (pin "1") (pinfunction "1_1") (pintype "passive"))
      (node (ref "U1") (pin "18") (pinfunction "AVCC_18") (pintype "bidirectional"))
      (node (ref "U1") (pin "4") (pinfunction "VCC_4") (pintype "bidirectional"))
      (node (ref "U1") (pin "6") (pinfunction "VCC_6") (pintype "bidirectional"))
    )
    (net (code "76") (name "V_BATT") (class "Default")
      (node (ref "C10") (pin "2") (pinfunction "2_2") (pintype "passive"))
      (node (ref "C11") (pin "2") (pinfunction "2_2") (pintype "passive"))
      (node (ref "C15") (pin "2") (pinfunction "2_2") (pintype "passive"))
      (node (ref "C22") (pin "2") (pinfunction "2_2") (pintype "passive"))
      (node (ref "C25") (pin "1") (pinfunction "+_1") (pintype "passive"))
      (node (ref "C3") (pin "1") (pinfunction "+_1") (pintype "passive"))
      (node (ref "CONN_BATT") (pin "P$1") (pinfunction "P_P$1") (pintype "bidirectional"))
      (node (ref "DFUH") (pin "C") (pinfunction "C_C") (pintype "passive"))
      (node (ref "DFVH") (pin "C") (pinfunction "C_C") (pintype "passive"))
      (node (ref "DFWH") (pin "C") (pinfunction "C_C") (pintype "passive"))
      (node (ref "IC1") (pin "3") (pinfunction "V+_3") (pintype "power_in"))
      (node (ref "IC5") (pin "12") (pinfunction "VDD_12") (pintype "bidirectional"))
      (node (ref "LPBAT") (pin "A") (pinfunction "A_A") (pintype "passive"))
      (node (ref "QUH") (pin "P$1") (pinfunction "D_P$1") (pintype "passive"))
      (node (ref "QUH") (pin "P$10") (pinfunction "D_P$10") (pintype "passive"))
      (node (ref "QUH") (pin "P$11") (pinfunction "D_P$11") (pintype "passive"))
      (node (ref "QUH") (pin "P$12") (pinfunction "D_P$12") (pintype "passive"))
      (node (ref "QUH") (pin "P$13") (pinfunction "D_P$13") (pintype "passive"))
      (node (ref "QUH") (pin "P$14") (pinfunction "D_P$14") (pintype "passive"))
      (node (ref "QUH") (pin "P$15") (pinfunction "D_P$15") (pintype "passive"))
      (node (ref "QUH") (pin "P$16") (pinfunction "D_P$16") (pintype "passive"))
      (node (ref "QUH") (pin "P$17") (pinfunction "D_P$17") (pintype "passive"))
      (node (ref "QUH") (pin "P$19") (pinfunction "D_P$19") (pintype "passive"))
      (node (ref "QUH") (pin "P$20") (pinfunction "D_P$20") (pintype "passive"))
      (node (ref "QUH") (pin "P$21") (pinfunction "D_P$21") (pintype "passive"))
      (node (ref "QUH") (pin "P$5") (pinfunction "D_P$5") (pintype "passive"))
      (node (ref "QUH") (pin "P$6") (pinfunction "D_P$6") (pintype "passive"))
      (node (ref "QUH") (pin "P$7") (pinfunction "D_P$7") (pintype "passive"))
      (node (ref "QUH") (pin "P$8") (pinfunction "D_P$8") (pintype "passive"))
      (node (ref "QUH") (pin "P$9") (pinfunction "D_P$9") (pintype "passive"))
      (node (ref "QVH") (pin "P$1") (pinfunction "D_P$1") (pintype "passive"))
      (node (ref "QVH") (pin "P$10") (pinfunction "D_P$10") (pintype "passive"))
      (node (ref "QVH") (pin "P$11") (pinfunction "D_P$11") (pintype "passive"))
      (node (ref "QVH") (pin "P$12") (pinfunction "D_P$12") (pintype "passive"))
      (node (ref "QVH") (pin "P$13") (pinfunction "D_P$13") (pintype "passive"))
      (node (ref "QVH") (pin "P$14") (pinfunction "D_P$14") (pintype "passive"))
      (node (ref "QVH") (pin "P$15") (pinfunction "D_P$15") (pintype "passive"))
      (node (ref "QVH") (pin "P$16") (pinfunction "D_P$16") (pintype "passive"))
      (node (ref "QVH") (pin "P$17") (pinfunction "D_P$17") (pintype "passive"))
      (node (ref "QVH") (pin "P$19") (pinfunction "D_P$19") (pintype "passive"))
      (node (ref "QVH") (pin "P$20") (pinfunction "D_P$20") (pintype "passive"))
      (node (ref "QVH") (pin "P$21") (pinfunction "D_P$21") (pintype "passive"))
      (node (ref "QVH") (pin "P$5") (pinfunction "D_P$5") (pintype "passive"))
      (node (ref "QVH") (pin "P$6") (pinfunction "D_P$6") (pintype "passive"))
      (node (ref "QVH") (pin "P$7") (pinfunction "D_P$7") (pintype "passive"))
      (node (ref "QVH") (pin "P$8") (pinfunction "D_P$8") (pintype "passive"))
      (node (ref "QVH") (pin "P$9") (pinfunction "D_P$9") (pintype "passive"))
      (node (ref "QWH") (pin "P$1") (pinfunction "D_P$1") (pintype "passive"))
      (node (ref "QWH") (pin "P$10") (pinfunction "D_P$10") (pintype "passive"))
      (node (ref "QWH") (pin "P$11") (pinfunction "D_P$11") (pintype "passive"))
      (node (ref "QWH") (pin "P$12") (pinfunction "D_P$12") (pintype "passive"))
      (node (ref "QWH") (pin "P$13") (pinfunction "D_P$13") (pintype "passive"))
      (node (ref "QWH") (pin "P$14") (pinfunction "D_P$14") (pintype "passive"))
      (node (ref "QWH") (pin "P$15") (pinfunction "D_P$15") (pintype "passive"))
      (node (ref "QWH") (pin "P$16") (pinfunction "D_P$16") (pintype "passive"))
      (node (ref "QWH") (pin "P$17") (pinfunction "D_P$17") (pintype "passive"))
      (node (ref "QWH") (pin "P$19") (pinfunction "D_P$19") (pintype "passive"))
      (node (ref "QWH") (pin "P$20") (pinfunction "D_P$20") (pintype "passive"))
      (node (ref "QWH") (pin "P$21") (pinfunction "D_P$21") (pintype "passive"))
      (node (ref "QWH") (pin "P$5") (pinfunction "D_P$5") (pintype "passive"))
      (node (ref "QWH") (pin "P$6") (pinfunction "D_P$6") (pintype "passive"))
      (node (ref "QWH") (pin "P$7") (pinfunction "D_P$7") (pintype "passive"))
      (node (ref "QWH") (pin "P$8") (pinfunction "D_P$8") (pintype "passive"))
      (node (ref "QWH") (pin "P$9") (pinfunction "D_P$9") (pintype "passive"))
      (node (ref "R31") (pin "1") (pinfunction "1_1") (pintype "passive"))
      (node (ref "RA1") (pin "5") (pinfunction "2_5") (pintype "passive"))
      (node (ref "RA1") (pin "6") (pinfunction "2_6") (pintype "passive"))
      (node (ref "RA1") (pin "7") (pinfunction "2_7") (pintype "passive"))
      (node (ref "RA1") (pin "8") (pinfunction "2_8") (pintype "passive"))
      (node (ref "RA7") (pin "5") (pinfunction "2_5") (pintype "passive"))
      (node (ref "RA7") (pin "6") (pinfunction "2_6") (pintype "passive"))
      (node (ref "RA7") (pin "7") (pinfunction "2_7") (pintype "passive"))
      (node (ref "RA7") (pin "8") (pinfunction "2_8") (pintype "passive"))
      (node (ref "RA9") (pin "2") (pinfunction "1_2") (pintype "passive"))
    )
    (net (code "77") (name "unconnected-(IC4A-X3-Pad11)") (class "Default")
      (node (ref "IC4") (pin "11") (pinfunction "X3_11") (pintype "bidirectional"))
    )
    (net (code "78") (name "unconnected-(IC4A-Y-Pad3)") (class "Default")
      (node (ref "IC4") (pin "3") (pinfunction "Y_3") (pintype "bidirectional"))
    )
    (net (code "79") (name "unconnected-(IC4A-Y0-Pad1)") (class "Default")
      (node (ref "IC4") (pin "1") (pinfunction "Y0_1") (pintype "bidirectional"))
    )
    (net (code "80") (name "unconnected-(IC4A-Y1-Pad5)") (class "Default")
      (node (ref "IC4") (pin "5") (pinfunction "Y1_5") (pintype "bidirectional"))
    )
    (net (code "81") (name "unconnected-(IC4A-Y2-Pad2)") (class "Default")
      (node (ref "IC4") (pin "2") (pinfunction "Y2_2") (pintype "bidirectional"))
    )
    (net (code "82") (name "unconnected-(IC4A-Y3-Pad4)") (class "Default")
      (node (ref "IC4") (pin "4") (pinfunction "Y3_4") (pintype "bidirectional"))
    )
    (net (code "83") (name "unconnected-(RA1-Pad1)") (class "Default")
      (node (ref "RA1") (pin "1") (pinfunction "1_1") (pintype "passive"))
    )
    (net (code "84") (name "unconnected-(RA5C-1-Pad3)") (class "Default")
      (node (ref "RA5") (pin "3") (pinfunction "1_3") (pintype "passive"))
    )
    (net (code "85") (name "unconnected-(RA5C-2-Pad6)") (class "Default")
      (node (ref "RA5") (pin "6") (pinfunction "2_6") (pintype "passive"))
    )
    (net (code "86") (name "unconnected-(RA5D-1-Pad4)") (class "Default")
      (node (ref "RA5") (pin "4") (pinfunction "1_4") (pintype "passive"))
    )
    (net (code "87") (name "unconnected-(RA5D-2-Pad5)") (class "Default")
      (node (ref "RA5") (pin "5") (pinfunction "2_5") (pintype "passive"))
    )
    (net (code "88") (name "unconnected-(RA6D-1-Pad4)") (class "Default")
      (node (ref "RA6") (pin "4") (pinfunction "1_4") (pintype "passive"))
    )
    (net (code "89") (name "unconnected-(RA6D-2-Pad5)") (class "Default")
      (node (ref "RA6") (pin "5") (pinfunction "2_5") (pintype "passive"))
    )
    (net (code "90") (name "unconnected-(RA7D-1-Pad4)") (class "Default")
      (node (ref "RA7") (pin "4") (pinfunction "1_4") (pintype "passive"))
    )
  )
)
